# Shifters.net
KiCad netlist of a schematic drawn in Altium Designer
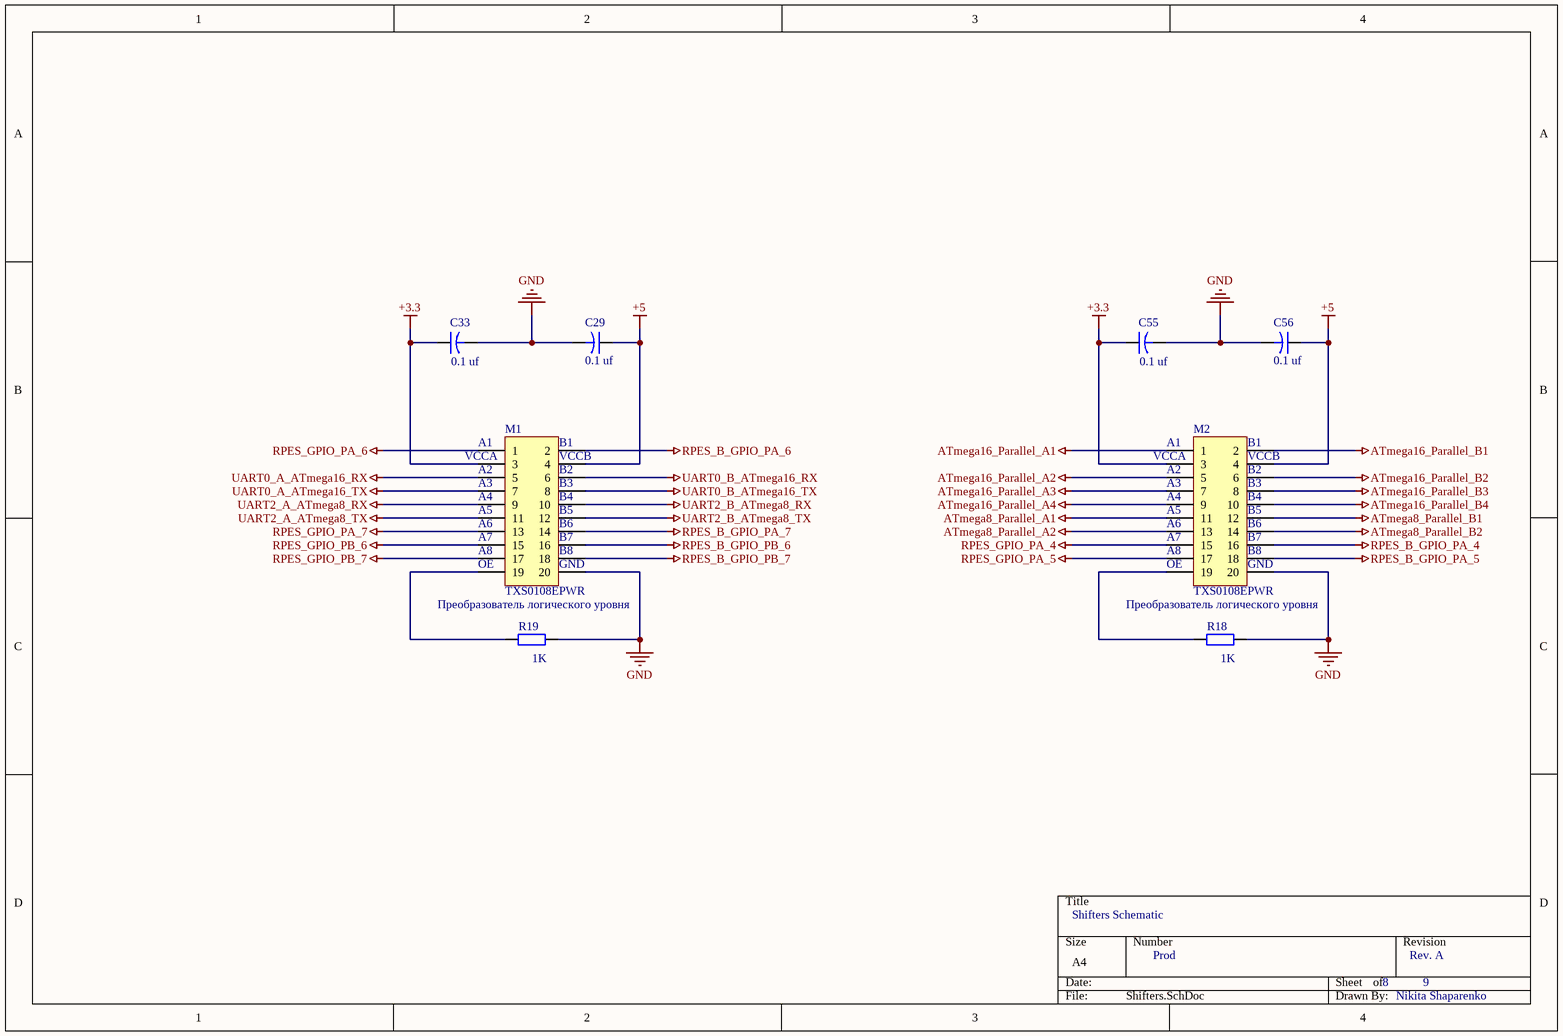
[diagram p0: Shifters.SchDoc]

(export (version "E")
  (design (tool "Eeschema 10.0.6"))
  (components
    (comp (ref "C29")
      (value "0.1 uf")
      (footprint "CAPR5-4X5")
      (description "Capacitor")
      (fields (field (name "Comment") "Cap2") (field (name "PUBLISHER") "Altium Limited"))
      (libsource (lib "Miscellaneous Devices") (part "Cap2"))
    )
    (comp (ref "C33")
      (value "0.1 uf")
      (footprint "CAPR5-4X5")
      (description "Capacitor")
      (fields (field (name "Comment") "Cap2") (field (name "PUBLISHER") "Altium Limited"))
      (libsource (lib "Miscellaneous Devices") (part "Cap2"))
    )
    (comp (ref "C55")
      (value "0.1 uf")
      (footprint "CAPR5-4X5")
      (description "Capacitor")
      (fields (field (name "Comment") "Cap2") (field (name "PUBLISHER") "Altium Limited"))
      (libsource (lib "Miscellaneous Devices") (part "Cap2"))
    )
    (comp (ref "C56")
      (value "0.1 uf")
      (footprint "CAPR5-4X5")
      (description "Capacitor")
      (fields (field (name "Comment") "Cap2") (field (name "PUBLISHER") "Altium Limited"))
      (libsource (lib "Miscellaneous Devices") (part "Cap2"))
    )
    (comp (ref "M1")
      (value "TXS0108EPWR")
      (footprint "TSSOP20")
      (description "Header, 10-Pin, Dual row")
      (fields (field (name "PUBLISHER") "Altium Limited"))
      (libsource (lib "Miscellaneous Connectors") (part "Header 10X2"))
    )
    (comp (ref "M2")
      (value "TXS0108EPWR")
      (footprint "TSSOP20")
      (description "Header, 10-Pin, Dual row")
      (fields (field (name "PUBLISHER") "Altium Limited"))
      (libsource (lib "Miscellaneous Connectors") (part "Header 10X2"))
    )
    (comp (ref "R18")
      (value "1K")
      (footprint "AXIAL-0.4")
      (description "Resistor")
      (fields (field (name "Comment") "Res2") (field (name "PUBLISHER") "Altium Limited"))
      (libsource (lib "Miscellaneous Devices") (part "Res2"))
    )
    (comp (ref "R19")
      (value "1K")
      (footprint "AXIAL-0.4")
      (description "Resistor")
      (fields (field (name "Comment") "Res2") (field (name "PUBLISHER") "Altium Limited"))
      (libsource (lib "Miscellaneous Devices") (part "Res2"))
    )
  )
  (nets
    (net (code "1") (name "+3.3") (class "Default")
      (node (ref "C33") (pin "1") (pinfunction "1_1") (pintype "passive"))
      (node (ref "C55") (pin "1") (pinfunction "1_1") (pintype "passive"))
      (node (ref "M1") (pin "3") (pinfunction "3_3") (pintype "passive"))
      (node (ref "M2") (pin "3") (pinfunction "3_3") (pintype "passive"))
    )
    (net (code "2") (name "+5") (class "Default")
      (node (ref "C29") (pin "1") (pinfunction "1_1") (pintype "passive"))
      (node (ref "C56") (pin "1") (pinfunction "1_1") (pintype "passive"))
      (node (ref "M1") (pin "4") (pinfunction "4_4") (pintype "passive"))
      (node (ref "M2") (pin "4") (pinfunction "4_4") (pintype "passive"))
    )
    (net (code "3") (name "ATmega8_Parallel_A1") (class "Default")
      (node (ref "M2") (pin "11") (pinfunction "11_11") (pintype "passive"))
    )
    (net (code "4") (name "ATmega8_Parallel_A2") (class "Default")
      (node (ref "M2") (pin "13") (pinfunction "13_13") (pintype "passive"))
    )
    (net (code "5") (name "ATmega8_Parallel_B1") (class "Default")
      (node (ref "M2") (pin "12") (pinfunction "12_12") (pintype "passive"))
    )
    (net (code "6") (name "ATmega8_Parallel_B2") (class "Default")
      (node (ref "M2") (pin "14") (pinfunction "14_14") (pintype "passive"))
    )
    (net (code "7") (name "ATmega16_Parallel_A1") (class "Default")
      (node (ref "M2") (pin "1") (pinfunction "1_1") (pintype "passive"))
    )
    (net (code "8") (name "ATmega16_Parallel_A2") (class "Default")
      (node (ref "M2") (pin "5") (pinfunction "5_5") (pintype "passive"))
    )
    (net (code "9") (name "ATmega16_Parallel_A3") (class "Default")
      (node (ref "M2") (pin "7") (pinfunction "7_7") (pintype "passive"))
    )
    (net (code "10") (name "ATmega16_Parallel_A4") (class "Default")
      (node (ref "M2") (pin "9") (pinfunction "9_9") (pintype "passive"))
    )
    (net (code "11") (name "ATmega16_Parallel_B1") (class "Default")
      (node (ref "M2") (pin "2") (pinfunction "2_2") (pintype "passive"))
    )
    (net (code "12") (name "ATmega16_Parallel_B2") (class "Default")
      (node (ref "M2") (pin "6") (pinfunction "6_6") (pintype "passive"))
    )
    (net (code "13") (name "ATmega16_Parallel_B3") (class "Default")
      (node (ref "M2") (pin "8") (pinfunction "8_8") (pintype "passive"))
    )
    (net (code "14") (name "ATmega16_Parallel_B4") (class "Default")
      (node (ref "M2") (pin "10") (pinfunction "10_10") (pintype "passive"))
    )
    (net (code "15") (name "GND") (class "Default")
      (node (ref "C29") (pin "2") (pinfunction "2_2") (pintype "passive"))
      (node (ref "C33") (pin "2") (pinfunction "2_2") (pintype "passive"))
      (node (ref "C55") (pin "2") (pinfunction "2_2") (pintype "passive"))
      (node (ref "C56") (pin "2") (pinfunction "2_2") (pintype "passive"))
      (node (ref "M1") (pin "20") (pinfunction "20_20") (pintype "passive"))
      (node (ref "M2") (pin "20") (pinfunction "20_20") (pintype "passive"))
      (node (ref "R18") (pin "2") (pinfunction "2_2") (pintype "passive"))
      (node (ref "R19") (pin "2") (pinfunction "2_2") (pintype "passive"))
    )
    (net (code "16") (name "Net-(M1-Pad19)") (class "Default")
      (node (ref "M1") (pin "19") (pinfunction "19_19") (pintype "passive"))
      (node (ref "R19") (pin "1") (pinfunction "1_1") (pintype "passive"))
    )
    (net (code "17") (name "Net-(M2-Pad19)") (class "Default")
      (node (ref "M2") (pin "19") (pinfunction "19_19") (pintype "passive"))
      (node (ref "R18") (pin "1") (pinfunction "1_1") (pintype "passive"))
    )
    (net (code "18") (name "RPES_B_GPIO_PA_4") (class "Default")
      (node (ref "M2") (pin "16") (pinfunction "16_16") (pintype "passive"))
    )
    (net (code "19") (name "RPES_B_GPIO_PA_5") (class "Default")
      (node (ref "M2") (pin "18") (pinfunction "18_18") (pintype "passive"))
    )
    (net (code "20") (name "RPES_B_GPIO_PA_6") (class "Default")
      (node (ref "M1") (pin "2") (pinfunction "2_2") (pintype "passive"))
    )
    (net (code "21") (name "RPES_B_GPIO_PA_7") (class "Default")
      (node (ref "M1") (pin "14") (pinfunction "14_14") (pintype "passive"))
    )
    (net (code "22") (name "RPES_B_GPIO_PB_6") (class "Default")
      (node (ref "M1") (pin "16") (pinfunction "16_16") (pintype "passive"))
    )
    (net (code "23") (name "RPES_B_GPIO_PB_7") (class "Default")
      (node (ref "M1") (pin "18") (pinfunction "18_18") (pintype "passive"))
    )
    (net (code "24") (name "RPES_GPIO_PA_4") (class "Default")
      (node (ref "M2") (pin "15") (pinfunction "15_15") (pintype "passive"))
    )
    (net (code "25") (name "RPES_GPIO_PA_5") (class "Default")
      (node (ref "M2") (pin "17") (pinfunction "17_17") (pintype "passive"))
    )
    (net (code "26") (name "RPES_GPIO_PA_6") (class "Default")
      (node (ref "M1") (pin "1") (pinfunction "1_1") (pintype "passive"))
    )
    (net (code "27") (name "RPES_GPIO_PA_7") (class "Default")
      (node (ref "M1") (pin "13") (pinfunction "13_13") (pintype "passive"))
    )
    (net (code "28") (name "RPES_GPIO_PB_6") (class "Default")
      (node (ref "M1") (pin "15") (pinfunction "15_15") (pintype "passive"))
    )
    (net (code "29") (name "RPES_GPIO_PB_7") (class "Default")
      (node (ref "M1") (pin "17") (pinfunction "17_17") (pintype "passive"))
    )
    (net (code "30") (name "UART0_A_ATmega16_RX") (class "Default")
      (node (ref "M1") (pin "5") (pinfunction "5_5") (pintype "passive"))
    )
    (net (code "31") (name "UART0_A_ATmega16_TX") (class "Default")
      (node (ref "M1") (pin "7") (pinfunction "7_7") (pintype "passive"))
    )
    (net (code "32") (name "UART0_B_ATmega16_RX") (class "Default")
      (node (ref "M1") (pin "6") (pinfunction "6_6") (pintype "passive"))
    )
    (net (code "33") (name "UART0_B_ATmega16_TX") (class "Default")
      (node (ref "M1") (pin "8") (pinfunction "8_8") (pintype "passive"))
    )
    (net (code "34") (name "UART2_A_ATmega8_RX") (class "Default")
      (node (ref "M1") (pin "9") (pinfunction "9_9") (pintype "passive"))
    )
    (net (code "35") (name "UART2_A_ATmega8_TX") (class "Default")
      (node (ref "M1") (pin "11") (pinfunction "11_11") (pintype "passive"))
    )
    (net (code "36") (name "UART2_B_ATmega8_RX") (class "Default")
      (node (ref "M1") (pin "10") (pinfunction "10_10") (pintype "passive"))
    )
    (net (code "37") (name "UART2_B_ATmega8_TX") (class "Default")
      (node (ref "M1") (pin "12") (pinfunction "12_12") (pintype "passive"))
    )
  )
)
